# Sheet1.net
KiCad netlist of a schematic drawn in Altium Designer
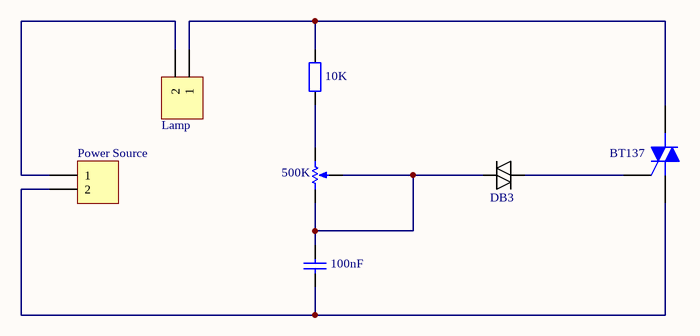
[diagram p0: Sheet1.SchDoc]

(export (version "E")
  (design (tool "Eeschema 10.0.6"))
  (components
    (comp (ref "C1")
      (value "100nF")
      (footprint "RAD-0.3")
      (description "Capacitor")
      (fields (field (name "Comment") "Cap") (field (name "PUBLISHER") "Altium Limited"))
      (libsource (lib "Miscellaneous Devices") (part "Cap"))
    )
    (comp (ref "D1")
      (value "DB3")
      (footprint "*DIOAD810W51L378D176P")
      (description "Rectifier Diode, 30 V, 34 V, 15 A, 2 A, DO-204AH, 2")
      (fields (field (name "MP") "DB3TG") (field (name "MF") "ON Semiconductor"))
      (libsource (lib "DB3TG") (part "DB3TG"))
    )
    (comp (ref "D2")
      (value "BT137")
      (footprint "369-03")
      (description "Silicon Bidirectional Triode Thyristor")
      (fields (field (name "PUBLISHER") "Altium Limited"))
      (libsource (lib "Miscellaneous Devices") (part "Triac"))
    )
    (comp (ref "H1")
      (value "Power Source")
      (footprint "HDR1X2")
      (description "Header, 2-Pin")
      (fields (field (name "PUBLISHER") "Altium Limited"))
      (libsource (lib "Miscellaneous Connectors") (part "Header 2"))
    )
    (comp (ref "H2")
      (value "Lamp")
      (footprint "HDR1X2")
      (description "Header, 2-Pin")
      (fields (field (name "PUBLISHER") "Altium Limited"))
      (libsource (lib "") (part "Header 2_1"))
    )
    (comp (ref "POT1")
      (value "500K")
      (footprint "VR5")
      (description "Potentiometer")
      (fields (field (name "Comment") "RPot") (field (name "PUBLISHER") "Altium Limited"))
      (libsource (lib "Miscellaneous Devices") (part "RPot"))
    )
    (comp (ref "R1")
      (value "10K")
      (footprint "AXIAL-0.4")
      (description "Resistor")
      (fields (field (name "Comment") "Res2") (field (name "PUBLISHER") "Altium Limited"))
      (libsource (lib "Miscellaneous Devices") (part "Res2"))
    )
  )
  (nets
    (net (code "1") (name "Net-(D2-G)") (class "Default")
      (node (ref "D1") (pin "2") (pinfunction "2_2") (pintype "passive"))
      (node (ref "D2") (pin "3") (pinfunction "G_3") (pintype "passive"))
    )
    (net (code "2") (name "Net-(D2-M1)") (class "Default")
      (node (ref "C1") (pin "2") (pinfunction "2_2") (pintype "passive"))
      (node (ref "D2") (pin "1") (pinfunction "M1_1") (pintype "passive"))
      (node (ref "H1") (pin "2") (pinfunction "2_2") (pintype "passive"))
    )
    (net (code "3") (name "Net-(D2-M2)") (class "Default")
      (node (ref "D2") (pin "2") (pinfunction "M2_2") (pintype "passive"))
      (node (ref "H2") (pin "1") (pinfunction "1_1") (pintype "passive"))
      (node (ref "R1") (pin "2") (pinfunction "2_2") (pintype "passive"))
    )
    (net (code "4") (name "Net-(H1-Pad1)") (class "Default")
      (node (ref "H1") (pin "1") (pinfunction "1_1") (pintype "passive"))
      (node (ref "H2") (pin "2") (pinfunction "2_2") (pintype "passive"))
    )
    (net (code "5") (name "Net-(POT1-BOT)") (class "Default")
      (node (ref "POT1") (pin "2") (pinfunction "BOT_2") (pintype "passive"))
      (node (ref "R1") (pin "1") (pinfunction "1_1") (pintype "passive"))
    )
    (net (code "6") (name "Net-(POT1-TAP)") (class "Default")
      (node (ref "C1") (pin "1") (pinfunction "1_1") (pintype "passive"))
      (node (ref "D1") (pin "1") (pinfunction "1_1") (pintype "passive"))
      (node (ref "POT1") (pin "1") (pinfunction "TOP_1") (pintype "passive"))
      (node (ref "POT1") (pin "3") (pinfunction "TAP_3") (pintype "passive"))
    )
  )
)
